# RK3399_Side_of_LPDDR4_Controller.net
KiCad netlist of a schematic drawn in Altium Designer
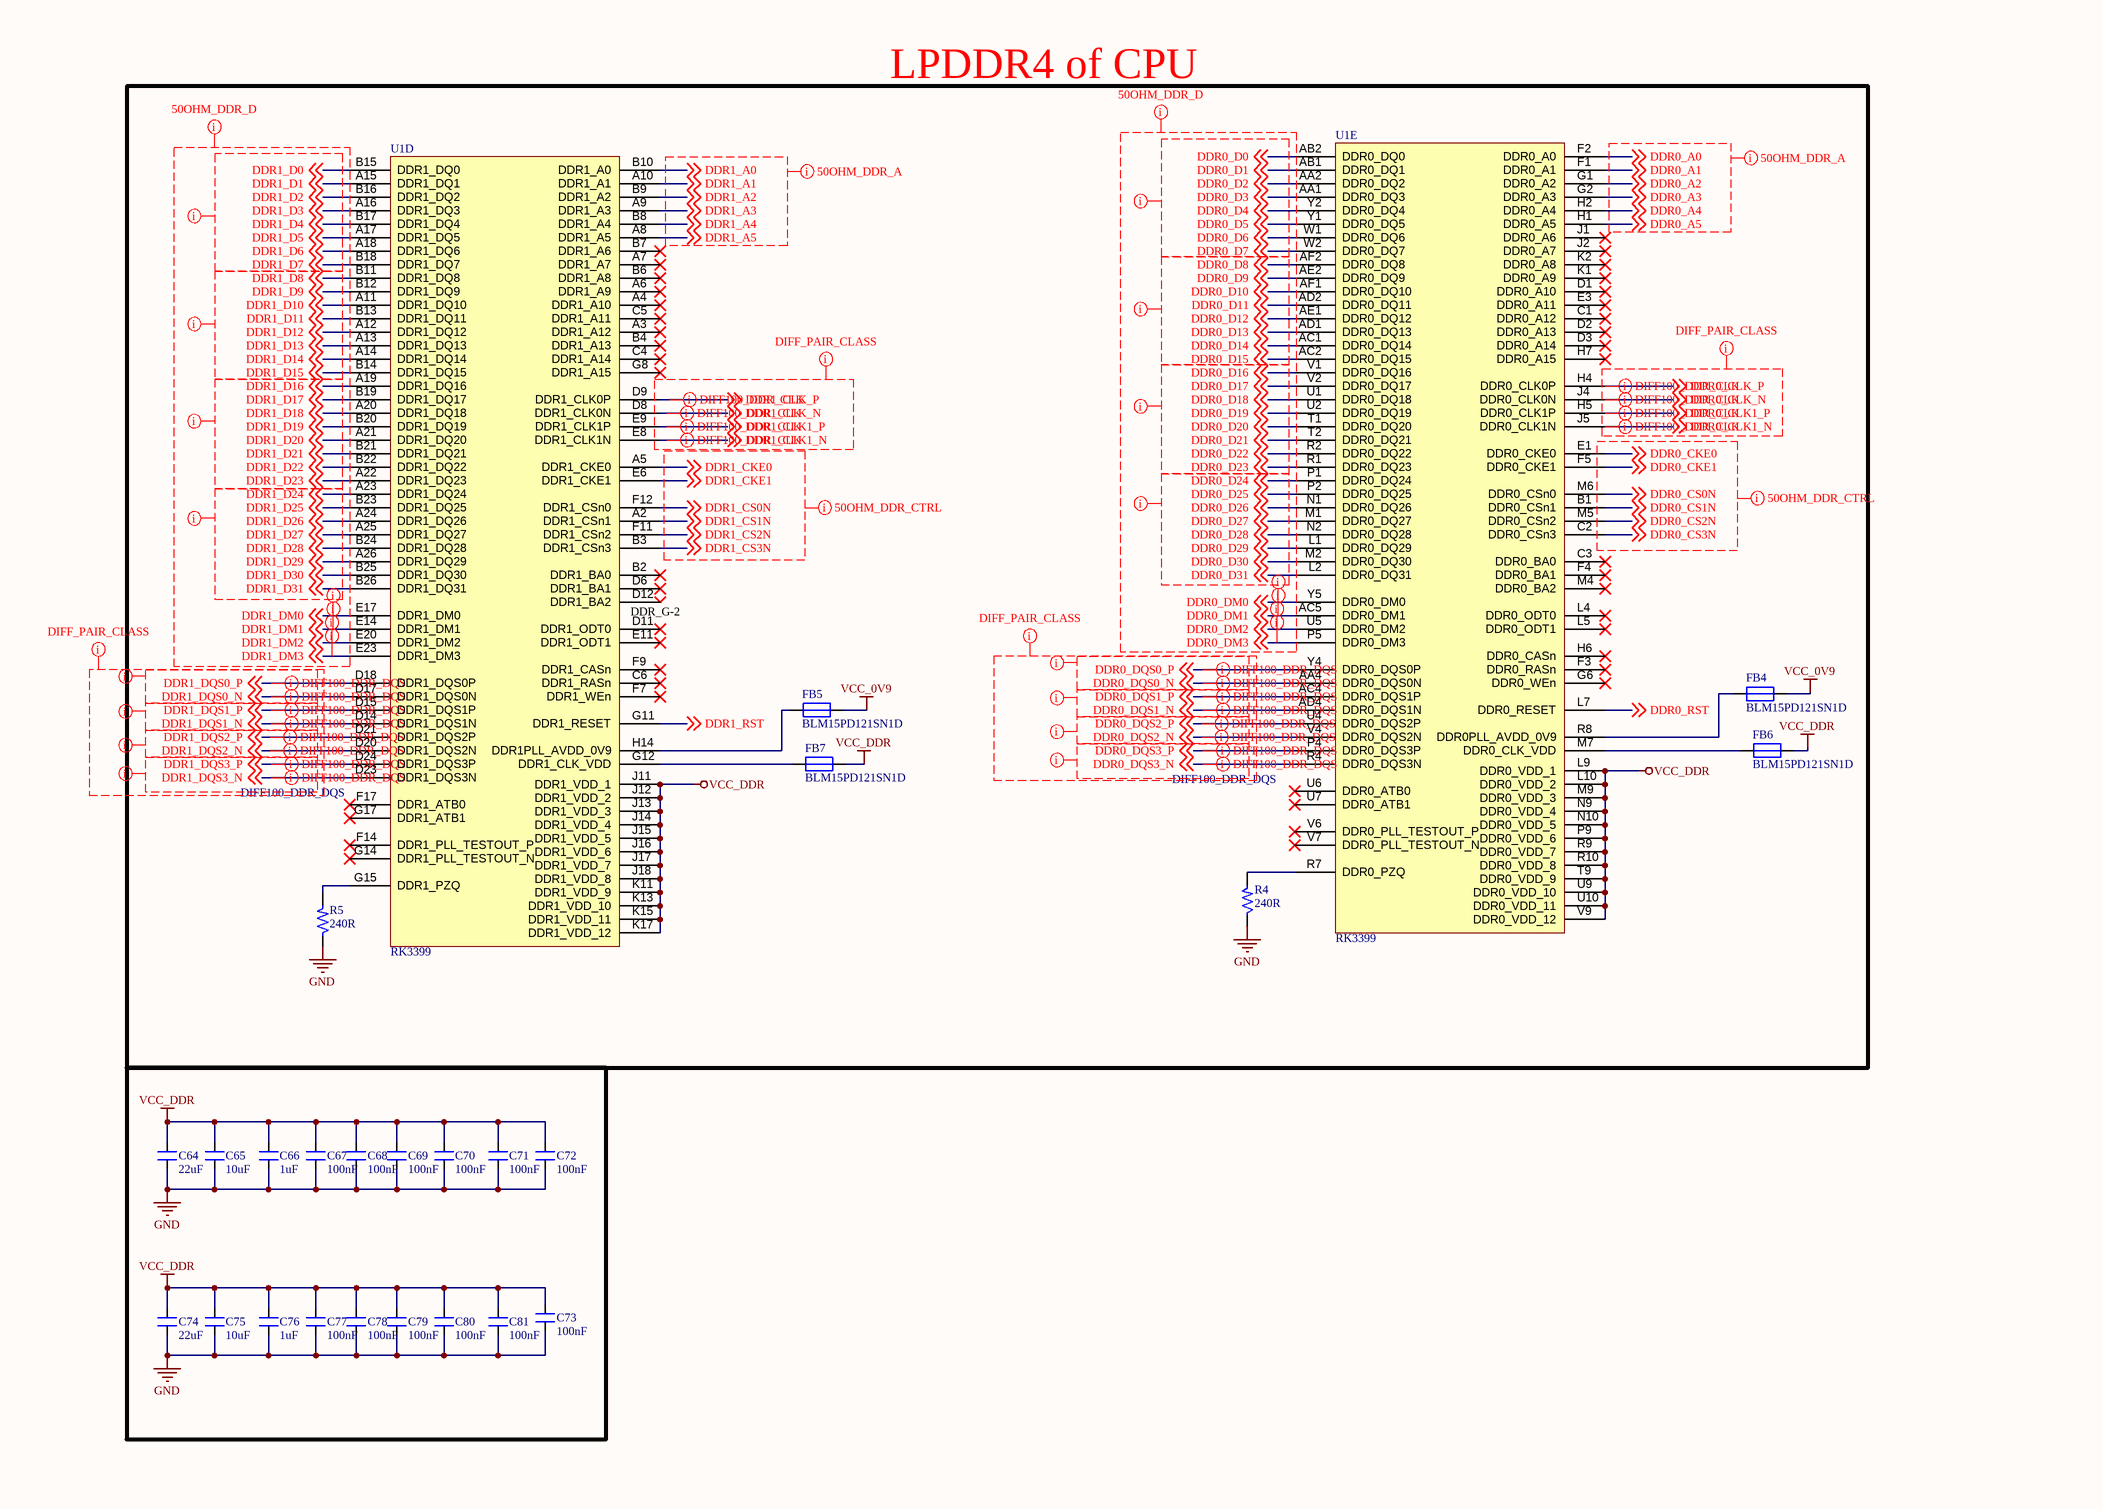
[diagram p0: RK3399 Side of LPDDR4 Controller.SchDoc]

(export (version "E")
  (design (tool "Eeschema 10.0.6"))
  (components
    (comp (ref "C64")
      (value "22uF")
      (footprint "CAP_0402")
      (description "22µF ±20% 6.3V Ceramic Capacitor X5R 0402 (1005 Metric)")
      (fields
        (field (name "MANUFACTURER") "Murata Electronics")
        (field (name "MANUFACTURER PART NUMBER") "CL05A226MQ5N6J8")
      )
      (libsource (lib "RK3399 _Module_Intlib") (part "CAP_22uF-6.3V-20%-0402"))
    )
    (comp (ref "C65")
      (value "10uF")
      (footprint "CAP_0402")
      (description "10µF ±20% 10V Ceramic Capacitor X5R 0402 (1005 Metric)")
      (fields
        (field (name "MANUFACTURER PART NUMBER") "CL05A106MP5NUNC")
        (field (name "MANUFACTURER") "Samsung Electro-Mechanics")
      )
      (libsource (lib "RK3399 _Module_Schlib") (part "CAP_10uF-10V-20%-0402"))
    )
    (comp (ref "C66")
      (value "1uF")
      (footprint "CAP_0201")
      (description "1µF ±20% 16V Ceramic Capacitor X5R 0201 (0603 Metric)")
      (fields
        (field (name "MANUFACTURER") "Samsung Electro-Mechanics")
        (field (name "MANUFACTURER PART NUMBER") "CL03A105MO3NRNH")
      )
      (libsource (lib "RK3399 _Module_Intlib") (part "CAP_1uF-16V-10%-0201"))
    )
    (comp (ref "C67")
      (value "100nF")
      (footprint "CAP_0201")
      (description "0.1µF ±10% 25V Ceramic Capacitor X5R 0201 (0603 Metric)")
      (fields
        (field (name "MANUFACTURER") "TDK Corporation")
        (field (name "MANUFACTURER PART NUMBER") "C0603X5R1E104K030BB")
      )
      (libsource (lib "RK3399 _Module_Intlib") (part "CAP_100nF-25V-10%-0201"))
    )
    (comp (ref "C68")
      (value "100nF")
      (footprint "CAP_0201")
      (description "0.1µF ±10% 25V Ceramic Capacitor X5R 0201 (0603 Metric)")
      (fields
        (field (name "MANUFACTURER") "TDK Corporation")
        (field (name "MANUFACTURER PART NUMBER") "C0603X5R1E104K030BB")
      )
      (libsource (lib "RK3399 _Module_Intlib") (part "CAP_100nF-25V-10%-0201"))
    )
    (comp (ref "C69")
      (value "100nF")
      (footprint "CAP_0201")
      (description "0.1µF ±10% 25V Ceramic Capacitor X5R 0201 (0603 Metric)")
      (fields
        (field (name "MANUFACTURER") "TDK Corporation")
        (field (name "MANUFACTURER PART NUMBER") "C0603X5R1E104K030BB")
      )
      (libsource (lib "RK3399 _Module_Intlib") (part "CAP_100nF-25V-10%-0201"))
    )
    (comp (ref "C70")
      (value "100nF")
      (footprint "CAP_0201")
      (description "0.1µF ±10% 25V Ceramic Capacitor X5R 0201 (0603 Metric)")
      (fields
        (field (name "MANUFACTURER") "TDK Corporation")
        (field (name "MANUFACTURER PART NUMBER") "C0603X5R1E104K030BB")
      )
      (libsource (lib "RK3399 _Module_Intlib") (part "CAP_100nF-25V-10%-0201"))
    )
    (comp (ref "C71")
      (value "100nF")
      (footprint "CAP_0201")
      (description "0.1µF ±10% 25V Ceramic Capacitor X5R 0201 (0603 Metric)")
      (fields
        (field (name "MANUFACTURER") "TDK Corporation")
        (field (name "MANUFACTURER PART NUMBER") "C0603X5R1E104K030BB")
      )
      (libsource (lib "RK3399 _Module_Intlib") (part "CAP_100nF-25V-10%-0201"))
    )
    (comp (ref "C72")
      (value "100nF")
      (footprint "CAP_0201")
      (description "0.1µF ±10% 25V Ceramic Capacitor X5R 0201 (0603 Metric)")
      (fields
        (field (name "MANUFACTURER") "TDK Corporation")
        (field (name "MANUFACTURER PART NUMBER") "C0603X5R1E104K030BB")
      )
      (libsource (lib "RK3399 _Module_Intlib") (part "CAP_100nF-25V-10%-0201"))
    )
    (comp (ref "C73")
      (value "100nF")
      (footprint "CAP_0201")
      (description "0.1µF ±10% 25V Ceramic Capacitor X5R 0201 (0603 Metric)")
      (fields
        (field (name "MANUFACTURER") "TDK Corporation")
        (field (name "MANUFACTURER PART NUMBER") "C0603X5R1E104K030BB")
      )
      (libsource (lib "RK3399 _Module_Intlib") (part "CAP_100nF-25V-10%-0201"))
    )
    (comp (ref "C74")
      (value "22uF")
      (footprint "CAP_0402")
      (description "22µF ±20% 6.3V Ceramic Capacitor X5R 0402 (1005 Metric)")
      (fields
        (field (name "MANUFACTURER") "Murata Electronics")
        (field (name "MANUFACTURER PART NUMBER") "CL05A226MQ5N6J8")
      )
      (libsource (lib "RK3399 _Module_Intlib") (part "CAP_22uF-6.3V-20%-0402"))
    )
    (comp (ref "C75")
      (value "10uF")
      (footprint "CAP_0402")
      (description "10µF ±20% 10V Ceramic Capacitor X5R 0402 (1005 Metric)")
      (fields
        (field (name "MANUFACTURER PART NUMBER") "CL05A106MP5NUNC")
        (field (name "MANUFACTURER") "Samsung Electro-Mechanics")
      )
      (libsource (lib "RK3399 _Module_Schlib") (part "CAP_10uF-10V-20%-0402"))
    )
    (comp (ref "C76")
      (value "1uF")
      (footprint "CAP_0201")
      (description "1µF ±20% 16V Ceramic Capacitor X5R 0201 (0603 Metric)")
      (fields
        (field (name "MANUFACTURER") "Samsung Electro-Mechanics")
        (field (name "MANUFACTURER PART NUMBER") "CL03A105MO3NRNH")
      )
      (libsource (lib "RK3399 _Module_Intlib") (part "CAP_1uF-16V-10%-0201"))
    )
    (comp (ref "C77")
      (value "100nF")
      (footprint "CAP_0201")
      (description "0.1µF ±10% 25V Ceramic Capacitor X5R 0201 (0603 Metric)")
      (fields
        (field (name "MANUFACTURER") "TDK Corporation")
        (field (name "MANUFACTURER PART NUMBER") "C0603X5R1E104K030BB")
      )
      (libsource (lib "RK3399 _Module_Intlib") (part "CAP_100nF-25V-10%-0201"))
    )
    (comp (ref "C78")
      (value "100nF")
      (footprint "CAP_0201")
      (description "0.1µF ±10% 25V Ceramic Capacitor X5R 0201 (0603 Metric)")
      (fields
        (field (name "MANUFACTURER") "TDK Corporation")
        (field (name "MANUFACTURER PART NUMBER") "C0603X5R1E104K030BB")
      )
      (libsource (lib "RK3399 _Module_Intlib") (part "CAP_100nF-25V-10%-0201"))
    )
    (comp (ref "C79")
      (value "100nF")
      (footprint "CAP_0201")
      (description "0.1µF ±10% 25V Ceramic Capacitor X5R 0201 (0603 Metric)")
      (fields
        (field (name "MANUFACTURER") "TDK Corporation")
        (field (name "MANUFACTURER PART NUMBER") "C0603X5R1E104K030BB")
      )
      (libsource (lib "RK3399 _Module_Intlib") (part "CAP_100nF-25V-10%-0201"))
    )
    (comp (ref "C80")
      (value "100nF")
      (footprint "CAP_0201")
      (description "0.1µF ±10% 25V Ceramic Capacitor X5R 0201 (0603 Metric)")
      (fields
        (field (name "MANUFACTURER") "TDK Corporation")
        (field (name "MANUFACTURER PART NUMBER") "C0603X5R1E104K030BB")
      )
      (libsource (lib "RK3399 _Module_Intlib") (part "CAP_100nF-25V-10%-0201"))
    )
    (comp (ref "C81")
      (value "100nF")
      (footprint "CAP_0201")
      (description "0.1µF ±10% 25V Ceramic Capacitor X5R 0201 (0603 Metric)")
      (fields
        (field (name "MANUFACTURER") "TDK Corporation")
        (field (name "MANUFACTURER PART NUMBER") "C0603X5R1E104K030BB")
      )
      (libsource (lib "RK3399 _Module_Intlib") (part "CAP_100nF-25V-10%-0201"))
    )
    (comp (ref "FB4")
      (value "BLM15PD121SN1D")
      (footprint "RES_0402")
      (description "120 Ohms @ 100MHz 1 Power Line Ferrite Bead 0402 (1005 Metric) 1.3A 90mOhm")
      (fields (field (name "MANUFACTURER") "Murata Electronics"))
      (libsource (lib "RK3399 _Module_Schlib") (part "FB_120R-1.3A-100Mhz-0402"))
    )
    (comp (ref "FB5")
      (value "BLM15PD121SN1D")
      (footprint "RES_0402")
      (description "120 Ohms @ 100MHz 1 Power Line Ferrite Bead 0402 (1005 Metric) 1.3A 90mOhm")
      (fields (field (name "MANUFACTURER") "Murata Electronics"))
      (libsource (lib "RK3399 _Module_Schlib") (part "FB_120R-1.3A-100Mhz-0402"))
    )
    (comp (ref "FB6")
      (value "BLM15PD121SN1D")
      (footprint "RES_0402")
      (description "120 Ohms @ 100MHz 1 Power Line Ferrite Bead 0402 (1005 Metric) 1.3A 90mOhm")
      (fields (field (name "MANUFACTURER") "Murata Electronics"))
      (libsource (lib "RK3399 _Module_Schlib") (part "FB_120R-1.3A-100Mhz-0402"))
    )
    (comp (ref "FB7")
      (value "BLM15PD121SN1D")
      (footprint "RES_0402")
      (description "120 Ohms @ 100MHz 1 Power Line Ferrite Bead 0402 (1005 Metric) 1.3A 90mOhm")
      (fields (field (name "MANUFACTURER") "Murata Electronics"))
      (libsource (lib "RK3399 _Module_Schlib") (part "FB_120R-1.3A-100Mhz-0402"))
    )
    (comp (ref "R4")
      (value "240R")
      (footprint "RES_0201")
      (description "240 Ohms ±1% 0.05W, 1/20W Chip Resistor 0201 (0603 Metric) Thick Film")
      (fields
        (field (name "MANUFACTURER") "Yageo")
        (field (name "MANUFACTURER PART NUMBER") "RC0201FR-07240RL")
      )
      (libsource (lib "RK3399 _Module_Intlib") (part "RES_240R-0.05W-1%-0201"))
    )
    (comp (ref "R5")
      (value "240R")
      (footprint "RES_0201")
      (description "240 Ohms ±1% 0.05W, 1/20W Chip Resistor 0201 (0603 Metric) Thick Film")
      (fields
        (field (name "MANUFACTURER") "Yageo")
        (field (name "MANUFACTURER PART NUMBER") "RC0201FR-07240RL")
      )
      (libsource (lib "RK3399 _Module_Intlib") (part "RES_240R-0.05W-1%-0201"))
    )
    (comp (ref "U1")
      (value "RK3399")
      (footprint "FBGA828_23_826X826")
      (description "RK3399 is a low power, high performance processor for computing, personal mobile.")
      (fields (field (name "MANUFACTURER") "Rockchip"))
      (libsource (lib "RK3399 _Module_Schlib") (part "IC_RK3399-FCBGA828"))
    )
  )
  (nets
    (net (code "1") (name "DDR0_A0") (class "Default")
      (node (ref "U1") (pin "F2") (pinfunction "DDR0_A0_F2") (pintype "passive"))
    )
    (net (code "2") (name "DDR0_A1") (class "Default")
      (node (ref "U1") (pin "F1") (pinfunction "DDR0_A1_F1") (pintype "passive"))
    )
    (net (code "3") (name "DDR0_A2") (class "Default")
      (node (ref "U1") (pin "G1") (pinfunction "DDR0_A2_G1") (pintype "passive"))
    )
    (net (code "4") (name "DDR0_A3") (class "Default")
      (node (ref "U1") (pin "G2") (pinfunction "DDR0_A3_G2") (pintype "passive"))
    )
    (net (code "5") (name "DDR0_A4") (class "Default")
      (node (ref "U1") (pin "H2") (pinfunction "DDR0_A4_H2") (pintype "passive"))
    )
    (net (code "6") (name "DDR0_A5") (class "Default")
      (node (ref "U1") (pin "H1") (pinfunction "DDR0_A5_H1") (pintype "passive"))
    )
    (net (code "7") (name "DDR0_CKE0") (class "Default")
      (node (ref "U1") (pin "E1") (pinfunction "DDR0_CKE0_E1") (pintype "passive"))
    )
    (net (code "8") (name "DDR0_CKE1") (class "Default")
      (node (ref "U1") (pin "F5") (pinfunction "DDR0_CKE1_F5") (pintype "passive"))
    )
    (net (code "9") (name "DDR0_CLK1_N") (class "Default")
      (node (ref "U1") (pin "J5") (pinfunction "DDR0_CLK1N_J5") (pintype "passive"))
    )
    (net (code "10") (name "DDR0_CLK1_P") (class "Default")
      (node (ref "U1") (pin "H5") (pinfunction "DDR0_CLK1P_H5") (pintype "passive"))
    )
    (net (code "11") (name "DDR0_CLK_N") (class "Default")
      (node (ref "U1") (pin "J4") (pinfunction "DDR0_CLK0N_J4") (pintype "passive"))
    )
    (net (code "12") (name "DDR0_CLK_P") (class "Default")
      (node (ref "U1") (pin "H4") (pinfunction "DDR0_CLK0P_H4") (pintype "passive"))
    )
    (net (code "13") (name "DDR0_CS0N") (class "Default")
      (node (ref "U1") (pin "M6") (pinfunction "DDR0_CSn0_M6") (pintype "passive"))
    )
    (net (code "14") (name "DDR0_CS1N") (class "Default")
      (node (ref "U1") (pin "B1") (pinfunction "DDR0_CSn1_B1") (pintype "passive"))
    )
    (net (code "15") (name "DDR0_CS2N") (class "Default")
      (node (ref "U1") (pin "M5") (pinfunction "DDR0_CSn2_M5") (pintype "passive"))
    )
    (net (code "16") (name "DDR0_CS3N") (class "Default")
      (node (ref "U1") (pin "C2") (pinfunction "DDR0_CSn3_C2") (pintype "passive"))
    )
    (net (code "17") (name "DDR0_D0") (class "Default")
      (node (ref "U1") (pin "AB2") (pinfunction "DDR0_DQ0_AB2") (pintype "passive"))
    )
    (net (code "18") (name "DDR0_D1") (class "Default")
      (node (ref "U1") (pin "AB1") (pinfunction "DDR0_DQ1_AB1") (pintype "passive"))
    )
    (net (code "19") (name "DDR0_D2") (class "Default")
      (node (ref "U1") (pin "AA2") (pinfunction "DDR0_DQ2_AA2") (pintype "passive"))
    )
    (net (code "20") (name "DDR0_D3") (class "Default")
      (node (ref "U1") (pin "AA1") (pinfunction "DDR0_DQ3_AA1") (pintype "passive"))
    )
    (net (code "21") (name "DDR0_D4") (class "Default")
      (node (ref "U1") (pin "Y2") (pinfunction "DDR0_DQ4_Y2") (pintype "passive"))
    )
    (net (code "22") (name "DDR0_D5") (class "Default")
      (node (ref "U1") (pin "Y1") (pinfunction "DDR0_DQ5_Y1") (pintype "passive"))
    )
    (net (code "23") (name "DDR0_D6") (class "Default")
      (node (ref "U1") (pin "W1") (pinfunction "DDR0_DQ6_W1") (pintype "passive"))
    )
    (net (code "24") (name "DDR0_D7") (class "Default")
      (node (ref "U1") (pin "W2") (pinfunction "DDR0_DQ7_W2") (pintype "passive"))
    )
    (net (code "25") (name "DDR0_D8") (class "Default")
      (node (ref "U1") (pin "AF2") (pinfunction "DDR0_DQ8_AF2") (pintype "passive"))
    )
    (net (code "26") (name "DDR0_D9") (class "Default")
      (node (ref "U1") (pin "AE2") (pinfunction "DDR0_DQ9_AE2") (pintype "passive"))
    )
    (net (code "27") (name "DDR0_D10") (class "Default")
      (node (ref "U1") (pin "AF1") (pinfunction "DDR0_DQ10_AF1") (pintype "passive"))
    )
    (net (code "28") (name "DDR0_D11") (class "Default")
      (node (ref "U1") (pin "AD2") (pinfunction "DDR0_DQ11_AD2") (pintype "passive"))
    )
    (net (code "29") (name "DDR0_D12") (class "Default")
      (node (ref "U1") (pin "AE1") (pinfunction "DDR0_DQ12_AE1") (pintype "passive"))
    )
    (net (code "30") (name "DDR0_D13") (class "Default")
      (node (ref "U1") (pin "AD1") (pinfunction "DDR0_DQ13_AD1") (pintype "passive"))
    )
    (net (code "31") (name "DDR0_D14") (class "Default")
      (node (ref "U1") (pin "AC1") (pinfunction "DDR0_DQ14_AC1") (pintype "passive"))
    )
    (net (code "32") (name "DDR0_D15") (class "Default")
      (node (ref "U1") (pin "AC2") (pinfunction "DDR0_DQ15_AC2") (pintype "passive"))
    )
    (net (code "33") (name "DDR0_D16") (class "Default")
      (node (ref "U1") (pin "V1") (pinfunction "DDR0_DQ16_V1") (pintype "passive"))
    )
    (net (code "34") (name "DDR0_D17") (class "Default")
      (node (ref "U1") (pin "V2") (pinfunction "DDR0_DQ17_V2") (pintype "passive"))
    )
    (net (code "35") (name "DDR0_D18") (class "Default")
      (node (ref "U1") (pin "U1") (pinfunction "DDR0_DQ18_U1") (pintype "passive"))
    )
    (net (code "36") (name "DDR0_D19") (class "Default")
      (node (ref "U1") (pin "U2") (pinfunction "DDR0_DQ19_U2") (pintype "passive"))
    )
    (net (code "37") (name "DDR0_D20") (class "Default")
      (node (ref "U1") (pin "T1") (pinfunction "DDR0_DQ20_T1") (pintype "passive"))
    )
    (net (code "38") (name "DDR0_D21") (class "Default")
      (node (ref "U1") (pin "T2") (pinfunction "DDR0_DQ21_T2") (pintype "passive"))
    )
    (net (code "39") (name "DDR0_D22") (class "Default")
      (node (ref "U1") (pin "R2") (pinfunction "DDR0_DQ22_R2") (pintype "passive"))
    )
    (net (code "40") (name "DDR0_D23") (class "Default")
      (node (ref "U1") (pin "R1") (pinfunction "DDR0_DQ23_R1") (pintype "passive"))
    )
    (net (code "41") (name "DDR0_D24") (class "Default")
      (node (ref "U1") (pin "P1") (pinfunction "DDR0_DQ24_P1") (pintype "passive"))
    )
    (net (code "42") (name "DDR0_D25") (class "Default")
      (node (ref "U1") (pin "P2") (pinfunction "DDR0_DQ25_P2") (pintype "passive"))
    )
    (net (code "43") (name "DDR0_D26") (class "Default")
      (node (ref "U1") (pin "N1") (pinfunction "DDR0_DQ26_N1") (pintype "passive"))
    )
    (net (code "44") (name "DDR0_D27") (class "Default")
      (node (ref "U1") (pin "M1") (pinfunction "DDR0_DQ27_M1") (pintype "passive"))
    )
    (net (code "45") (name "DDR0_D28") (class "Default")
      (node (ref "U1") (pin "N2") (pinfunction "DDR0_DQ28_N2") (pintype "passive"))
    )
    (net (code "46") (name "DDR0_D29") (class "Default")
      (node (ref "U1") (pin "L1") (pinfunction "DDR0_DQ29_L1") (pintype "passive"))
    )
    (net (code "47") (name "DDR0_D30") (class "Default")
      (node (ref "U1") (pin "M2") (pinfunction "DDR0_DQ30_M2") (pintype "passive"))
    )
    (net (code "48") (name "DDR0_D31") (class "Default")
      (node (ref "U1") (pin "L2") (pinfunction "DDR0_DQ31_L2") (pintype "passive"))
    )
    (net (code "49") (name "DDR0_DM0") (class "Default")
      (node (ref "U1") (pin "Y5") (pinfunction "DDR0_DM0_Y5") (pintype "passive"))
    )
    (net (code "50") (name "DDR0_DM1") (class "Default")
      (node (ref "U1") (pin "AC5") (pinfunction "DDR0_DM1_AC5") (pintype "passive"))
    )
    (net (code "51") (name "DDR0_DM2") (class "Default")
      (node (ref "U1") (pin "U5") (pinfunction "DDR0_DM2_U5") (pintype "passive"))
    )
    (net (code "52") (name "DDR0_DM3") (class "Default")
      (node (ref "U1") (pin "P5") (pinfunction "DDR0_DM3_P5") (pintype "passive"))
    )
    (net (code "53") (name "DDR0_DQS0_N") (class "Default")
      (node (ref "U1") (pin "AA4") (pinfunction "DDR0_DQS0N_AA4") (pintype "passive"))
    )
    (net (code "54") (name "DDR0_DQS0_P") (class "Default")
      (node (ref "U1") (pin "Y4") (pinfunction "DDR0_DQS0P_Y4") (pintype "passive"))
    )
    (net (code "55") (name "DDR0_DQS1_N") (class "Default")
      (node (ref "U1") (pin "AD4") (pinfunction "DDR0_DQS1N_AD4") (pintype "passive"))
    )
    (net (code "56") (name "DDR0_DQS1_P") (class "Default")
      (node (ref "U1") (pin "AC4") (pinfunction "DDR0_DQS1P_AC4") (pintype "passive"))
    )
    (net (code "57") (name "DDR0_DQS2_N") (class "Default")
      (node (ref "U1") (pin "V4") (pinfunction "DDR0_DQS2N_V4") (pintype "passive"))
    )
    (net (code "58") (name "DDR0_DQS2_P") (class "Default")
      (node (ref "U1") (pin "U4") (pinfunction "DDR0_DQS2P_U4") (pintype "passive"))
    )
    (net (code "59") (name "DDR0_DQS3_N") (class "Default")
      (node (ref "U1") (pin "R4") (pinfunction "DDR0_DQS3N_R4") (pintype "passive"))
    )
    (net (code "60") (name "DDR0_DQS3_P") (class "Default")
      (node (ref "U1") (pin "P4") (pinfunction "DDR0_DQS3P_P4") (pintype "passive"))
    )
    (net (code "61") (name "DDR0_RST") (class "Default")
      (node (ref "U1") (pin "L7") (pinfunction "DDR0_RESET_L7") (pintype "passive"))
    )
    (net (code "62") (name "DDR1_A0") (class "Default")
      (node (ref "U1") (pin "B10") (pinfunction "DDR1_A0_B10") (pintype "passive"))
    )
    (net (code "63") (name "DDR1_A1") (class "Default")
      (node (ref "U1") (pin "A10") (pinfunction "DDR1_A1_A10") (pintype "passive"))
    )
    (net (code "64") (name "DDR1_A2") (class "Default")
      (node (ref "U1") (pin "B9") (pinfunction "DDR1_A2_B9") (pintype "passive"))
    )
    (net (code "65") (name "DDR1_A3") (class "Default")
      (node (ref "U1") (pin "A9") (pinfunction "DDR1_A3_A9") (pintype "passive"))
    )
    (net (code "66") (name "DDR1_A4") (class "Default")
      (node (ref "U1") (pin "B8") (pinfunction "DDR1_A4_B8") (pintype "passive"))
    )
    (net (code "67") (name "DDR1_A5") (class "Default")
      (node (ref "U1") (pin "A8") (pinfunction "DDR1_A5_A8") (pintype "passive"))
    )
    (net (code "68") (name "DDR1_CKE0") (class "Default")
      (node (ref "U1") (pin "A5") (pinfunction "DDR1_CKE0_A5") (pintype "passive"))
    )
    (net (code "69") (name "DDR1_CKE1") (class "Default")
      (node (ref "U1") (pin "E6") (pinfunction "DDR1_CKE1_E6") (pintype "passive"))
    )
    (net (code "70") (name "DDR1_CLK1_N") (class "Default")
      (node (ref "U1") (pin "E8") (pinfunction "DDR1_CLK1N_E8") (pintype "passive"))
    )
    (net (code "71") (name "DDR1_CLK1_P") (class "Default")
      (node (ref "U1") (pin "E9") (pinfunction "DDR1_CLK1P_E9") (pintype "passive"))
    )
    (net (code "72") (name "DDR1_CLK_N") (class "Default")
      (node (ref "U1") (pin "D8") (pinfunction "DDR1_CLK0N_D8") (pintype "passive"))
    )
    (net (code "73") (name "DDR1_CLK_P") (class "Default")
      (node (ref "U1") (pin "D9") (pinfunction "DDR1_CLK0P_D9") (pintype "passive"))
    )
    (net (code "74") (name "DDR1_CS0N") (class "Default")
      (node (ref "U1") (pin "F12") (pinfunction "DDR1_CSn0_F12") (pintype "passive"))
    )
    (net (code "75") (name "DDR1_CS1N") (class "Default")
      (node (ref "U1") (pin "A2") (pinfunction "DDR1_CSn1_A2") (pintype "passive"))
    )
    (net (code "76") (name "DDR1_CS2N") (class "Default")
      (node (ref "U1") (pin "F11") (pinfunction "DDR1_CSn2_F11") (pintype "passive"))
    )
    (net (code "77") (name "DDR1_CS3N") (class "Default")
      (node (ref "U1") (pin "B3") (pinfunction "DDR1_CSn3_B3") (pintype "passive"))
    )
    (net (code "78") (name "DDR1_D0") (class "Default")
      (node (ref "U1") (pin "B15") (pinfunction "DDR1_DQ0_B15") (pintype "passive"))
    )
    (net (code "79") (name "DDR1_D1") (class "Default")
      (node (ref "U1") (pin "A15") (pinfunction "DDR1_DQ1_A15") (pintype "passive"))
    )
    (net (code "80") (name "DDR1_D2") (class "Default")
      (node (ref "U1") (pin "B16") (pinfunction "DDR1_DQ2_B16") (pintype "passive"))
    )
    (net (code "81") (name "DDR1_D3") (class "Default")
      (node (ref "U1") (pin "A16") (pinfunction "DDR1_DQ3_A16") (pintype "passive"))
    )
    (net (code "82") (name "DDR1_D4") (class "Default")
      (node (ref "U1") (pin "B17") (pinfunction "DDR1_DQ4_B17") (pintype "passive"))
    )
    (net (code "83") (name "DDR1_D5") (class "Default")
      (node (ref "U1") (pin "A17") (pinfunction "DDR1_DQ5_A17") (pintype "passive"))
    )
    (net (code "84") (name "DDR1_D6") (class "Default")
      (node (ref "U1") (pin "A18") (pinfunction "DDR1_DQ6_A18") (pintype "passive"))
    )
    (net (code "85") (name "DDR1_D7") (class "Default")
      (node (ref "U1") (pin "B18") (pinfunction "DDR1_DQ7_B18") (pintype "passive"))
    )
    (net (code "86") (name "DDR1_D8") (class "Default")
      (node (ref "U1") (pin "B11") (pinfunction "DDR1_DQ8_B11") (pintype "passive"))
    )
    (net (code "87") (name "DDR1_D9") (class "Default")
      (node (ref "U1") (pin "B12") (pinfunction "DDR1_DQ9_B12") (pintype "passive"))
    )
    (net (code "88") (name "DDR1_D10") (class "Default")
      (node (ref "U1") (pin "A11") (pinfunction "DDR1_DQ10_A11") (pintype "passive"))
    )
    (net (code "89") (name "DDR1_D11") (class "Default")
      (node (ref "U1") (pin "B13") (pinfunction "DDR1_DQ11_B13") (pintype "passive"))
    )
    (net (code "90") (name "DDR1_D12") (class "Default")
      (node (ref "U1") (pin "A12") (pinfunction "DDR1_DQ12_A12") (pintype "passive"))
    )
    (net (code "91") (name "DDR1_D13") (class "Default")
      (node (ref "U1") (pin "A13") (pinfunction "DDR1_DQ13_A13") (pintype "passive"))
    )
    (net (code "92") (name "DDR1_D14") (class "Default")
      (node (ref "U1") (pin "A14") (pinfunction "DDR1_DQ14_A14") (pintype "passive"))
    )
    (net (code "93") (name "DDR1_D15") (class "Default")
      (node (ref "U1") (pin "B14") (pinfunction "DDR1_DQ15_B14") (pintype "passive"))
    )
    (net (code "94") (name "DDR1_D16") (class "Default")
      (node (ref "U1") (pin "A19") (pinfunction "DDR1_DQ16_A19") (pintype "passive"))
    )
    (net (code "95") (name "DDR1_D17") (class "Default")
      (node (ref "U1") (pin "B19") (pinfunction "DDR1_DQ17_B19") (pintype "passive"))
    )
    (net (code "96") (name "DDR1_D18") (class "Default")
      (node (ref "U1") (pin "A20") (pinfunction "DDR1_DQ18_A20") (pintype "passive"))
    )
    (net (code "97") (name "DDR1_D19") (class "Default")
      (node (ref "U1") (pin "B20") (pinfunction "DDR1_DQ19_B20") (pintype "passive"))
    )
    (net (code "98") (name "DDR1_D20") (class "Default")
      (node (ref "U1") (pin "A21") (pinfunction "DDR1_DQ20_A21") (pintype "passive"))
    )
    (net (code "99") (name "DDR1_D21") (class "Default")
      (node (ref "U1") (pin "B21") (pinfunction "DDR1_DQ21_B21") (pintype "passive"))
    )
    (net (code "100") (name "DDR1_D22") (class "Default")
      (node (ref "U1") (pin "B22") (pinfunction "DDR1_DQ22_B22") (pintype "passive"))
    )
    (net (code "101") (name "DDR1_D23") (class "Default")
      (node (ref "U1") (pin "A22") (pinfunction "DDR1_DQ23_A22") (pintype "passive"))
    )
    (net (code "102") (name "DDR1_D24") (class "Default")
      (node (ref "U1") (pin "A23") (pinfunction "DDR1_DQ24_A23") (pintype "passive"))
    )
    (net (code "103") (name "DDR1_D25") (class "Default")
      (node (ref "U1") (pin "B23") (pinfunction "DDR1_DQ25_B23") (pintype "passive"))
    )
    (net (code "104") (name "DDR1_D26") (class "Default")
      (node (ref "U1") (pin "A24") (pinfunction "DDR1_DQ26_A24") (pintype "passive"))
    )
    (net (code "105") (name "DDR1_D27") (class "Default")
      (node (ref "U1") (pin "A25") (pinfunction "DDR1_DQ27_A25") (pintype "passive"))
    )
    (net (code "106") (name "DDR1_D28") (class "Default")
      (node (ref "U1") (pin "B24") (pinfunction "DDR1_DQ28_B24") (pintype "passive"))
    )
    (net (code "107") (name "DDR1_D29") (class "Default")
      (node (ref "U1") (pin "A26") (pinfunction "DDR1_DQ29_A26") (pintype "passive"))
    )
    (net (code "108") (name "DDR1_D30") (class "Default")
      (node (ref "U1") (pin "B25") (pinfunction "DDR1_DQ30_B25") (pintype "passive"))
    )
    (net (code "109") (name "DDR1_D31") (class "Default")
      (node (ref "U1") (pin "B26") (pinfunction "DDR1_DQ31_B26") (pintype "passive"))
    )
    (net (code "110") (name "DDR1_DM0") (class "Default")
      (node (ref "U1") (pin "E17") (pinfunction "DDR1_DM0_E17") (pintype "passive"))
    )
    (net (code "111") (name "DDR1_DM1") (class "Default")
      (node (ref "U1") (pin "E14") (pinfunction "DDR1_DM1_E14") (pintype "passive"))
    )
    (net (code "112") (name "DDR1_DM2") (class "Default")
      (node (ref "U1") (pin "E20") (pinfunction "DDR1_DM2_E20") (pintype "passive"))
    )
    (net (code "113") (name "DDR1_DM3") (class "Default")
      (node (ref "U1") (pin "E23") (pinfunction "DDR1_DM3_E23") (pintype "passive"))
    )
    (net (code "114") (name "DDR1_DQS0_N") (class "Default")
      (node (ref "U1") (pin "D17") (pinfunction "DDR1_DQS0N_D17") (pintype "passive"))
    )
    (net (code "115") (name "DDR1_DQS0_P") (class "Default")
      (node (ref "U1") (pin "D18") (pinfunction "DDR1_DQS0P_D18") (pintype "passive"))
    )
    (net (code "116") (name "DDR1_DQS1_N") (class "Default")
      (node (ref "U1") (pin "D14") (pinfunction "DDR1_DQS1N_D14") (pintype "passive"))
    )
    (net (code "117") (name "DDR1_DQS1_P") (class "Default")
      (node (ref "U1") (pin "D15") (pinfunction "DDR1_DQS1P_D15") (pintype "passive"))
    )
    (net (code "118") (name "DDR1_DQS2_N") (class "Default")
      (node (ref "U1") (pin "D20") (pinfunction "DDR1_DQS2N_D20") (pintype "passive"))
    )
    (net (code "119") (name "DDR1_DQS2_P") (class "Default")
      (node (ref "U1") (pin "D21") (pinfunction "DDR1_DQS2P_D21") (pintype "passive"))
    )
    (net (code "120") (name "DDR1_DQS3_N") (class "Default")
      (node (ref "U1") (pin "D23") (pinfunction "DDR1_DQS3N_D23") (pintype "passive"))
    )
    (net (code "121") (name "DDR1_DQS3_P") (class "Default")
      (node (ref "U1") (pin "D24") (pinfunction "DDR1_DQS3P_D24") (pintype "passive"))
    )
    (net (code "122") (name "DDR1_RST") (class "Default")
      (node (ref "U1") (pin "G11") (pinfunction "DDR1_RESET_G11") (pintype "passive"))
    )
    (net (code "123") (name "GND") (class "Default")
      (node (ref "C64") (pin "1") (pinfunction "1_1") (pintype "passive"))
      (node (ref "C65") (pin "1") (pinfunction "1_1") (pintype "passive"))
      (node (ref "C66") (pin "1") (pinfunction "1_1") (pintype "passive"))
      (node (ref "C67") (pin "1") (pinfunction "1_1") (pintype "passive"))
      (node (ref "C68") (pin "1") (pinfunction "1_1") (pintype "passive"))
      (node (ref "C69") (pin "1") (pinfunction "1_1") (pintype "passive"))
      (node (ref "C70") (pin "1") (pinfunction "1_1") (pintype "passive"))
      (node (ref "C71") (pin "1") (pinfunction "1_1") (pintype "passive"))
      (node (ref "C72") (pin "1") (pinfunction "1_1") (pintype "passive"))
      (node (ref "C73") (pin "1") (pinfunction "1_1") (pintype "passive"))
      (node (ref "C74") (pin "1") (pinfunction "1_1") (pintype "passive"))
      (node (ref "C75") (pin "1") (pinfunction "1_1") (pintype "passive"))
      (node (ref "C76") (pin "1") (pinfunction "1_1") (pintype "passive"))
      (node (ref "C77") (pin "1") (pinfunction "1_1") (pintype "passive"))
      (node (ref "C78") (pin "1") (pinfunction "1_1") (pintype "passive"))
      (node (ref "C79") (pin "1") (pinfunction "1_1") (pintype "passive"))
      (node (ref "C80") (pin "1") (pinfunction "1_1") (pintype "passive"))
      (node (ref "C81") (pin "1") (pinfunction "1_1") (pintype "passive"))
      (node (ref "R4") (pin "1") (pinfunction "1_1") (pintype "passive"))
      (node (ref "R5") (pin "1") (pinfunction "1_1") (pintype "passive"))
    )
    (net (code "124") (name "Net-(U1D-DDR1PLL_AVDD_0V9)") (class "Default")
      (node (ref "FB5") (pin "1") (pinfunction "1_1") (pintype "passive"))
      (node (ref "U1") (pin "H14") (pinfunction "DDR1PLL_AVDD_0V9_H14") (pintype "passive"))
    )
    (net (code "125") (name "Net-(U1D-DDR1_CLK_VDD)") (class "Default")
      (node (ref "FB7") (pin "1") (pinfunction "1_1") (pintype "passive"))
      (node (ref "U1") (pin "G12") (pinfunction "DDR1_CLK_VDD_G12") (pintype "passive"))
    )
    (net (code "126") (name "Net-(U1D-DDR1_PZQ)") (class "Default")
      (node (ref "R5") (pin "2") (pinfunction "2_2") (pintype "passive"))
      (node (ref "U1") (pin "G15") (pinfunction "DDR1_PZQ_G15") (pintype "passive"))
    )
    (net (code "127") (name "Net-(U1E-DDR0PLL_AVDD_0V9)") (class "Default")
      (node (ref "FB4") (pin "1") (pinfunction "1_1") (pintype "passive"))
      (node (ref "U1") (pin "R8") (pinfunction "DDR0PLL_AVDD_0V9_R8") (pintype "passive"))
    )
    (net (code "128") (name "Net-(U1E-DDR0_CLK_VDD)") (class "Default")
      (node (ref "FB6") (pin "1") (pinfunction "1_1") (pintype "passive"))
      (node (ref "U1") (pin "M7") (pinfunction "DDR0_CLK_VDD_M7") (pintype "passive"))
    )
    (net (code "129") (name "Net-(U1E-DDR0_PZQ)") (class "Default")
      (node (ref "R4") (pin "2") (pinfunction "2_2") (pintype "passive"))
      (node (ref "U1") (pin "R7") (pinfunction "DDR0_PZQ_R7") (pintype "passive"))
    )
    (net (code "130") (name "VCC_0V9") (class "Default")
      (node (ref "FB4") (pin "2") (pinfunction "2_2") (pintype "passive"))
      (node (ref "FB5") (pin "2") (pinfunction "2_2") (pintype "passive"))
    )
    (net (code "131") (name "VCC_DDR") (class "Default")
      (node (ref "C64") (pin "2") (pinfunction "2_2") (pintype "passive"))
      (node (ref "C65") (pin "2") (pinfunction "2_2") (pintype "passive"))
      (node (ref "C66") (pin "2") (pinfunction "2_2") (pintype "passive"))
      (node (ref "C67") (pin "2") (pinfunction "2_2") (pintype "passive"))
      (node (ref "C68") (pin "2") (pinfunction "2_2") (pintype "passive"))
      (node (ref "C69") (pin "2") (pinfunction "2_2") (pintype "passive"))
      (node (ref "C70") (pin "2") (pinfunction "2_2") (pintype "passive"))
      (node (ref "C71") (pin "2") (pinfunction "2_2") (pintype "passive"))
      (node (ref "C72") (pin "2") (pinfunction "2_2") (pintype "passive"))
      (node (ref "C73") (pin "2") (pinfunction "2_2") (pintype "passive"))
      (node (ref "C74") (pin "2") (pinfunction "2_2") (pintype "passive"))
      (node (ref "C75") (pin "2") (pinfunction "2_2") (pintype "passive"))
      (node (ref "C76") (pin "2") (pinfunction "2_2") (pintype "passive"))
      (node (ref "C77") (pin "2") (pinfunction "2_2") (pintype "passive"))
      (node (ref "C78") (pin "2") (pinfunction "2_2") (pintype "passive"))
      (node (ref "C79") (pin "2") (pinfunction "2_2") (pintype "passive"))
      (node (ref "C80") (pin "2") (pinfunction "2_2") (pintype "passive"))
      (node (ref "C81") (pin "2") (pinfunction "2_2") (pintype "passive"))
      (node (ref "FB6") (pin "2") (pinfunction "2_2") (pintype "passive"))
      (node (ref "FB7") (pin "2") (pinfunction "2_2") (pintype "passive"))
      (node (ref "U1") (pin "J11") (pinfunction "DDR1_VDD_1_J11") (pintype "passive"))
      (node (ref "U1") (pin "J12") (pinfunction "DDR1_VDD_2_J12") (pintype "passive"))
      (node (ref "U1") (pin "J13") (pinfunction "DDR1_VDD_3_J13") (pintype "passive"))
      (node (ref "U1") (pin "J14") (pinfunction "DDR1_VDD_4_J14") (pintype "passive"))
      (node (ref "U1") (pin "J15") (pinfunction "DDR1_VDD_5_J15") (pintype "passive"))
      (node (ref "U1") (pin "J16") (pinfunction "DDR1_VDD_6_J16") (pintype "passive"))
      (node (ref "U1") (pin "J17") (pinfunction "DDR1_VDD_7_J17") (pintype "passive"))
      (node (ref "U1") (pin "J18") (pinfunction "DDR1_VDD_8_J18") (pintype "passive"))
      (node (ref "U1") (pin "K11") (pinfunction "DDR1_VDD_9_K11") (pintype "passive"))
      (node (ref "U1") (pin "K13") (pinfunction "DDR1_VDD_10_K13") (pintype "passive"))
      (node (ref "U1") (pin "K15") (pinfunction "DDR1_VDD_11_K15") (pintype "passive"))
      (node (ref "U1") (pin "K17") (pinfunction "DDR1_VDD_12_K17") (pintype "passive"))
      (node (ref "U1") (pin "L10") (pinfunction "DDR0_VDD_2_L10") (pintype "passive"))
      (node (ref "U1") (pin "L9") (pinfunction "DDR0_VDD_1_L9") (pintype "passive"))
      (node (ref "U1") (pin "M9") (pinfunction "DDR0_VDD_3_M9") (pintype "passive"))
      (node (ref "U1") (pin "N10") (pinfunction "DDR0_VDD_5_N10") (pintype "passive"))
      (node (ref "U1") (pin "N9") (pinfunction "DDR0_VDD_4_N9") (pintype "passive"))
      (node (ref "U1") (pin "P9") (pinfunction "DDR0_VDD_6_P9") (pintype "passive"))
      (node (ref "U1") (pin "R10") (pinfunction "DDR0_VDD_8_R10") (pintype "passive"))
      (node (ref "U1") (pin "R9") (pinfunction "DDR0_VDD_7_R9") (pintype "passive"))
      (node (ref "U1") (pin "T9") (pinfunction "DDR0_VDD_9_T9") (pintype "passive"))
      (node (ref "U1") (pin "U10") (pinfunction "DDR0_VDD_11_U10") (pintype "passive"))
      (node (ref "U1") (pin "U9") (pinfunction "DDR0_VDD_10_U9") (pintype "passive"))
      (node (ref "U1") (pin "V9") (pinfunction "DDR0_VDD_12_V9") (pintype "passive"))
    )
    (net (code "132") (name "unconnected-(U1D-DDR1_A6-PadB7)") (class "Default")
      (node (ref "U1") (pin "B7") (pinfunction "DDR1_A6_B7") (pintype "passive+no_connect"))
    )
    (net (code "133") (name "unconnected-(U1D-DDR1_A7-PadA7)") (class "Default")
      (node (ref "U1") (pin "A7") (pinfunction "DDR1_A7_A7") (pintype "passive+no_connect"))
    )
    (net (code "134") (name "unconnected-(U1D-DDR1_A8-PadB6)") (class "Default")
      (node (ref "U1") (pin "B6") (pinfunction "DDR1_A8_B6") (pintype "passive+no_connect"))
    )
    (net (code "135") (name "unconnected-(U1D-DDR1_A9-PadA6)") (class "Default")
      (node (ref "U1") (pin "A6") (pinfunction "DDR1_A9_A6") (pintype "passive+no_connect"))
    )
    (net (code "136") (name "unconnected-(U1D-DDR1_A10-PadA4)") (class "Default")
      (node (ref "U1") (pin "A4") (pinfunction "DDR1_A10_A4") (pintype "passive+no_connect"))
    )
    (net (code "137") (name "unconnected-(U1D-DDR1_A11-PadC5)") (class "Default")
      (node (ref "U1") (pin "C5") (pinfunction "DDR1_A11_C5") (pintype "passive+no_connect"))
    )
    (net (code "138") (name "unconnected-(U1D-DDR1_A12-PadA3)") (class "Default")
      (node (ref "U1") (pin "A3") (pinfunction "DDR1_A12_A3") (pintype "passive+no_connect"))
    )
    (net (code "139") (name "unconnected-(U1D-DDR1_A13-PadB4)") (class "Default")
      (node (ref "U1") (pin "B4") (pinfunction "DDR1_A13_B4") (pintype "passive+no_connect"))
    )
    (net (code "140") (name "unconnected-(U1D-DDR1_A14-PadC4)") (class "Default")
      (node (ref "U1") (pin "C4") (pinfunction "DDR1_A14_C4") (pintype "passive+no_connect"))
    )
    (net (code "141") (name "unconnected-(U1D-DDR1_A15-PadG8)") (class "Default")
      (node (ref "U1") (pin "G8") (pinfunction "DDR1_A15_G8") (pintype "passive+no_connect"))
    )
    (net (code "142") (name "unconnected-(U1D-DDR1_ATB0-PadF17)") (class "Default")
      (node (ref "U1") (pin "F17") (pinfunction "DDR1_ATB0_F17") (pintype "passive+no_connect"))
    )
    (net (code "143") (name "unconnected-(U1D-DDR1_ATB1-PadG17)") (class "Default")
      (node (ref "U1") (pin "G17") (pinfunction "DDR1_ATB1_G17") (pintype "passive+no_connect"))
    )
    (net (code "144") (name "unconnected-(U1D-DDR1_BA0-PadB2)") (class "Default")
      (node (ref "U1") (pin "B2") (pinfunction "DDR1_BA0_B2") (pintype "passive+no_connect"))
    )
    (net (code "145") (name "unconnected-(U1D-DDR1_BA1-PadD6)") (class "Default")
      (node (ref "U1") (pin "D6") (pinfunction "DDR1_BA1_D6") (pintype "passive+no_connect"))
    )
    (net (code "146") (name "unconnected-(U1D-DDR1_BA2-PadD12)") (class "Default")
      (node (ref "U1") (pin "D12") (pinfunction "DDR1_BA2_D12") (pintype "passive+no_connect"))
    )
    (net (code "147") (name "unconnected-(U1D-DDR1_CASn-PadF9)") (class "Default")
      (node (ref "U1") (pin "F9") (pinfunction "DDR1_CASn_F9") (pintype "passive+no_connect"))
    )
    (net (code "148") (name "unconnected-(U1D-DDR1_ODT0-PadD11)") (class "Default")
      (node (ref "U1") (pin "D11") (pinfunction "DDR1_ODT0_D11") (pintype "passive+no_connect"))
    )
    (net (code "149") (name "unconnected-(U1D-DDR1_ODT1-PadE11)") (class "Default")
      (node (ref "U1") (pin "E11") (pinfunction "DDR1_ODT1_E11") (pintype "passive+no_connect"))
    )
    (net (code "150") (name "unconnected-(U1D-DDR1_PLL_TESTOUT_N-PadG14)") (class "Default")
      (node (ref "U1") (pin "G14") (pinfunction "DDR1_PLL_TESTOUT_N_G14") (pintype "passive+no_connect"))
    )
    (net (code "151") (name "unconnected-(U1D-DDR1_PLL_TESTOUT_P-PadF14)") (class "Default")
      (node (ref "U1") (pin "F14") (pinfunction "DDR1_PLL_TESTOUT_P_F14") (pintype "passive+no_connect"))
    )
    (net (code "152") (name "unconnected-(U1D-DDR1_RASn-PadC6)") (class "Default")
      (node (ref "U1") (pin "C6") (pinfunction "DDR1_RASn_C6") (pintype "passive+no_connect"))
    )
    (net (code "153") (name "unconnected-(U1D-DDR1_WEn-PadF7)") (class "Default")
      (node (ref "U1") (pin "F7") (pinfunction "DDR1_WEn_F7") (pintype "passive+no_connect"))
    )
    (net (code "154") (name "unconnected-(U1E-DDR0_A6-PadJ1)") (class "Default")
      (node (ref "U1") (pin "J1") (pinfunction "DDR0_A6_J1") (pintype "passive+no_connect"))
    )
    (net (code "155") (name "unconnected-(U1E-DDR0_A7-PadJ2)") (class "Default")
      (node (ref "U1") (pin "J2") (pinfunction "DDR0_A7_J2") (pintype "passive+no_connect"))
    )
    (net (code "156") (name "unconnected-(U1E-DDR0_A8-PadK2)") (class "Default")
      (node (ref "U1") (pin "K2") (pinfunction "DDR0_A8_K2") (pintype "passive+no_connect"))
    )
    (net (code "157") (name "unconnected-(U1E-DDR0_A9-PadK1)") (class "Default")
      (node (ref "U1") (pin "K1") (pinfunction "DDR0_A9_K1") (pintype "passive+no_connect"))
    )
    (net (code "158") (name "unconnected-(U1E-DDR0_A10-PadD1)") (class "Default")
      (node (ref "U1") (pin "D1") (pinfunction "DDR0_A10_D1") (pintype "passive+no_connect"))
    )
    (net (code "159") (name "unconnected-(U1E-DDR0_A11-PadE3)") (class "Default")
      (node (ref "U1") (pin "E3") (pinfunction "DDR0_A11_E3") (pintype "passive+no_connect"))
    )
    (net (code "160") (name "unconnected-(U1E-DDR0_A12-PadC1)") (class "Default")
      (node (ref "U1") (pin "C1") (pinfunction "DDR0_A12_C1") (pintype "passive+no_connect"))
    )
    (net (code "161") (name "unconnected-(U1E-DDR0_A13-PadD2)") (class "Default")
      (node (ref "U1") (pin "D2") (pinfunction "DDR0_A13_D2") (pintype "passive+no_connect"))
    )
    (net (code "162") (name "unconnected-(U1E-DDR0_A14-PadD3)") (class "Default")
      (node (ref "U1") (pin "D3") (pinfunction "DDR0_A14_D3") (pintype "passive+no_connect"))
    )
    (net (code "163") (name "unconnected-(U1E-DDR0_A15-PadH7)") (class "Default")
      (node (ref "U1") (pin "H7") (pinfunction "DDR0_A15_H7") (pintype "passive+no_connect"))
    )
    (net (code "164") (name "unconnected-(U1E-DDR0_ATB0-PadU6)") (class "Default")
      (node (ref "U1") (pin "U6") (pinfunction "DDR0_ATB0_U6") (pintype "passive+no_connect"))
    )
    (net (code "165") (name "unconnected-(U1E-DDR0_ATB1-PadU7)") (class "Default")
      (node (ref "U1") (pin "U7") (pinfunction "DDR0_ATB1_U7") (pintype "passive+no_connect"))
    )
    (net (code "166") (name "unconnected-(U1E-DDR0_BA0-PadC3)") (class "Default")
      (node (ref "U1") (pin "C3") (pinfunction "DDR0_BA0_C3") (pintype "passive+no_connect"))
    )
    (net (code "167") (name "unconnected-(U1E-DDR0_BA1-PadF4)") (class "Default")
      (node (ref "U1") (pin "F4") (pinfunction "DDR0_BA1_F4") (pintype "passive+no_connect"))
    )
    (net (code "168") (name "unconnected-(U1E-DDR0_BA2-PadM4)") (class "Default")
      (node (ref "U1") (pin "M4") (pinfunction "DDR0_BA2_M4") (pintype "passive+no_connect"))
    )
    (net (code "169") (name "unconnected-(U1E-DDR0_CASn-PadH6)") (class "Default")
      (node (ref "U1") (pin "H6") (pinfunction "DDR0_CASn_H6") (pintype "passive+no_connect"))
    )
    (net (code "170") (name "unconnected-(U1E-DDR0_ODT0-PadL4)") (class "Default")
      (node (ref "U1") (pin "L4") (pinfunction "DDR0_ODT0_L4") (pintype "passive+no_connect"))
    )
    (net (code "171") (name "unconnected-(U1E-DDR0_ODT1-PadL5)") (class "Default")
      (node (ref "U1") (pin "L5") (pinfunction "DDR0_ODT1_L5") (pintype "passive+no_connect"))
    )
    (net (code "172") (name "unconnected-(U1E-DDR0_PLL_TESTOUT_N-PadV7)") (class "Default")
      (node (ref "U1") (pin "V7") (pinfunction "DDR0_PLL_TESTOUT_N_V7") (pintype "passive+no_connect"))
    )
    (net (code "173") (name "unconnected-(U1E-DDR0_PLL_TESTOUT_P-PadV6)") (class "Default")
      (node (ref "U1") (pin "V6") (pinfunction "DDR0_PLL_TESTOUT_P_V6") (pintype "passive+no_connect"))
    )
    (net (code "174") (name "unconnected-(U1E-DDR0_RASn-PadF3)") (class "Default")
      (node (ref "U1") (pin "F3") (pinfunction "DDR0_RASn_F3") (pintype "passive+no_connect"))
    )
    (net (code "175") (name "unconnected-(U1E-DDR0_WEn-PadG6)") (class "Default")
      (node (ref "U1") (pin "G6") (pinfunction "DDR0_WEn_G6") (pintype "passive+no_connect"))
    )
  )
)
